# exixe_pogo.net
KiCad netlist of a schematic drawn in EAGLE
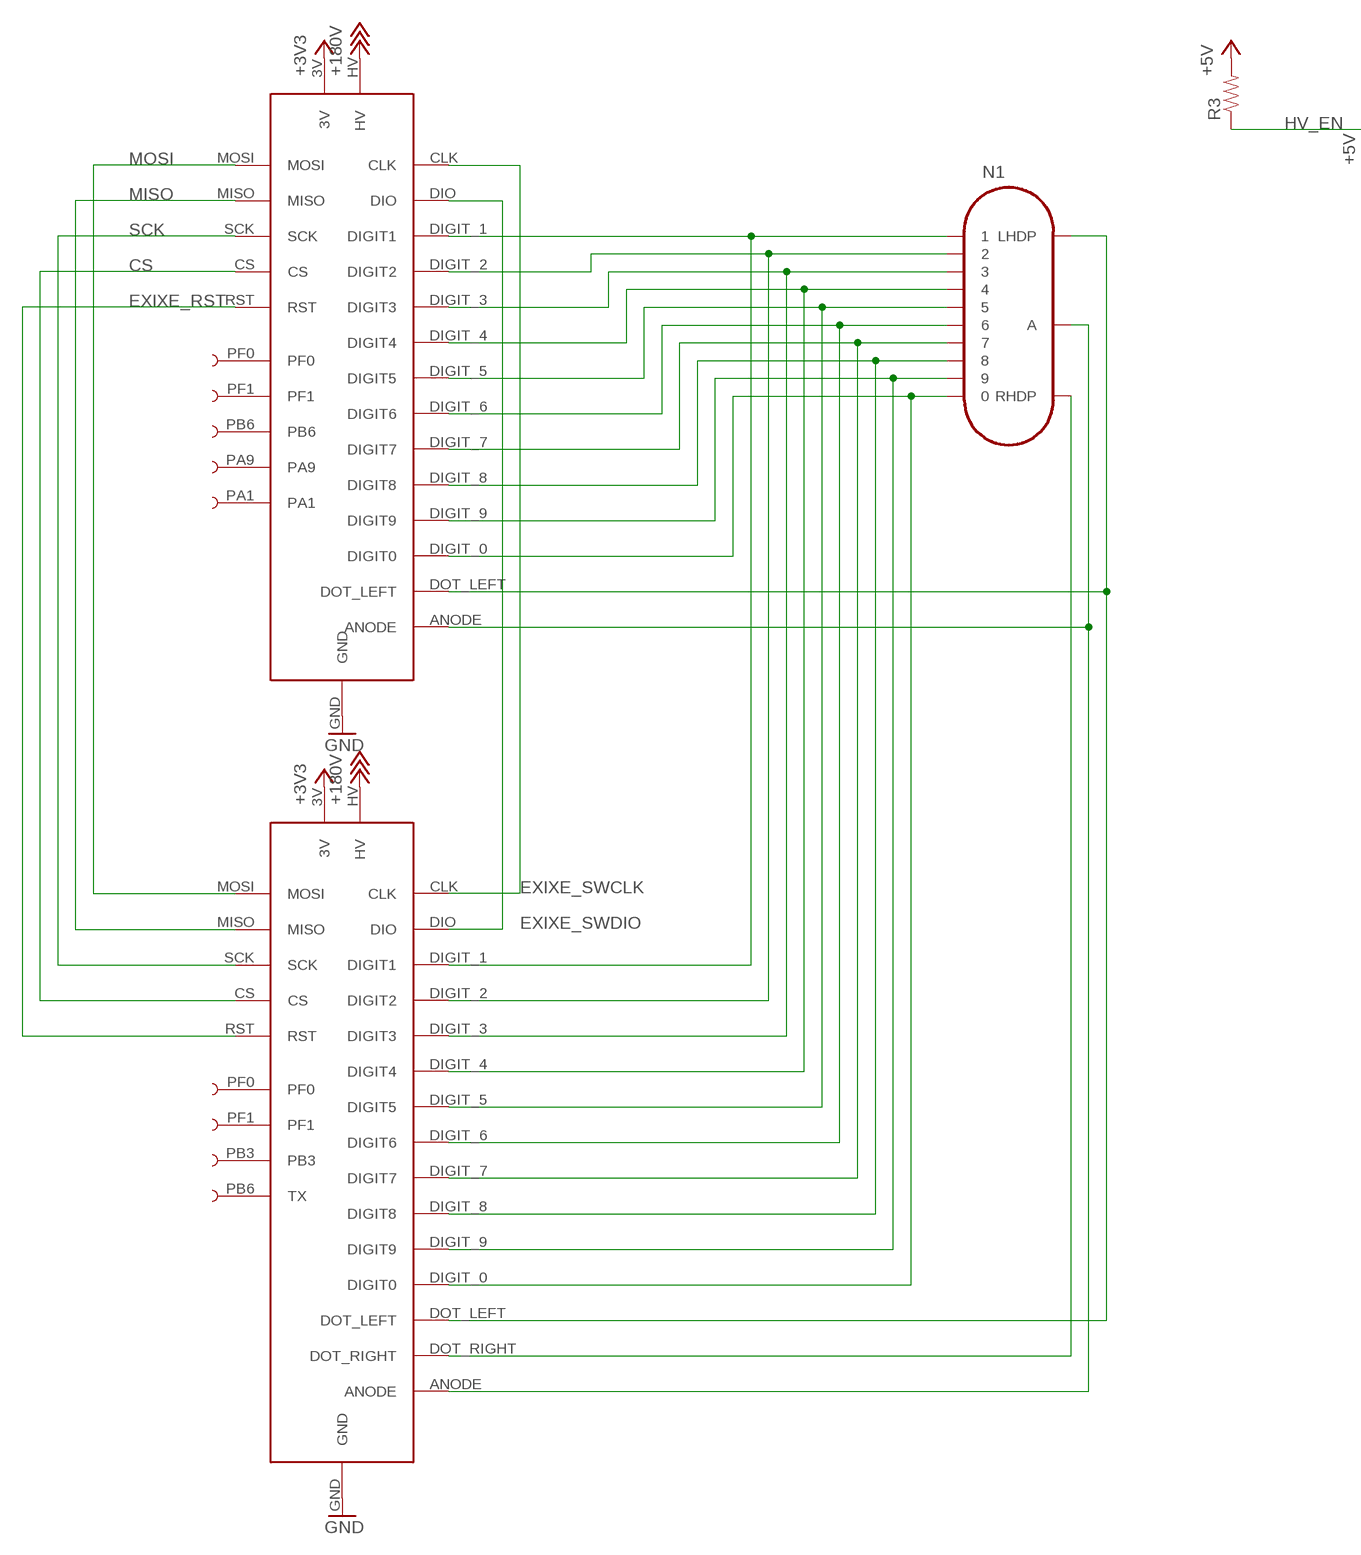
[diagram p0: schematic, sheet 1, part 1 of 2]
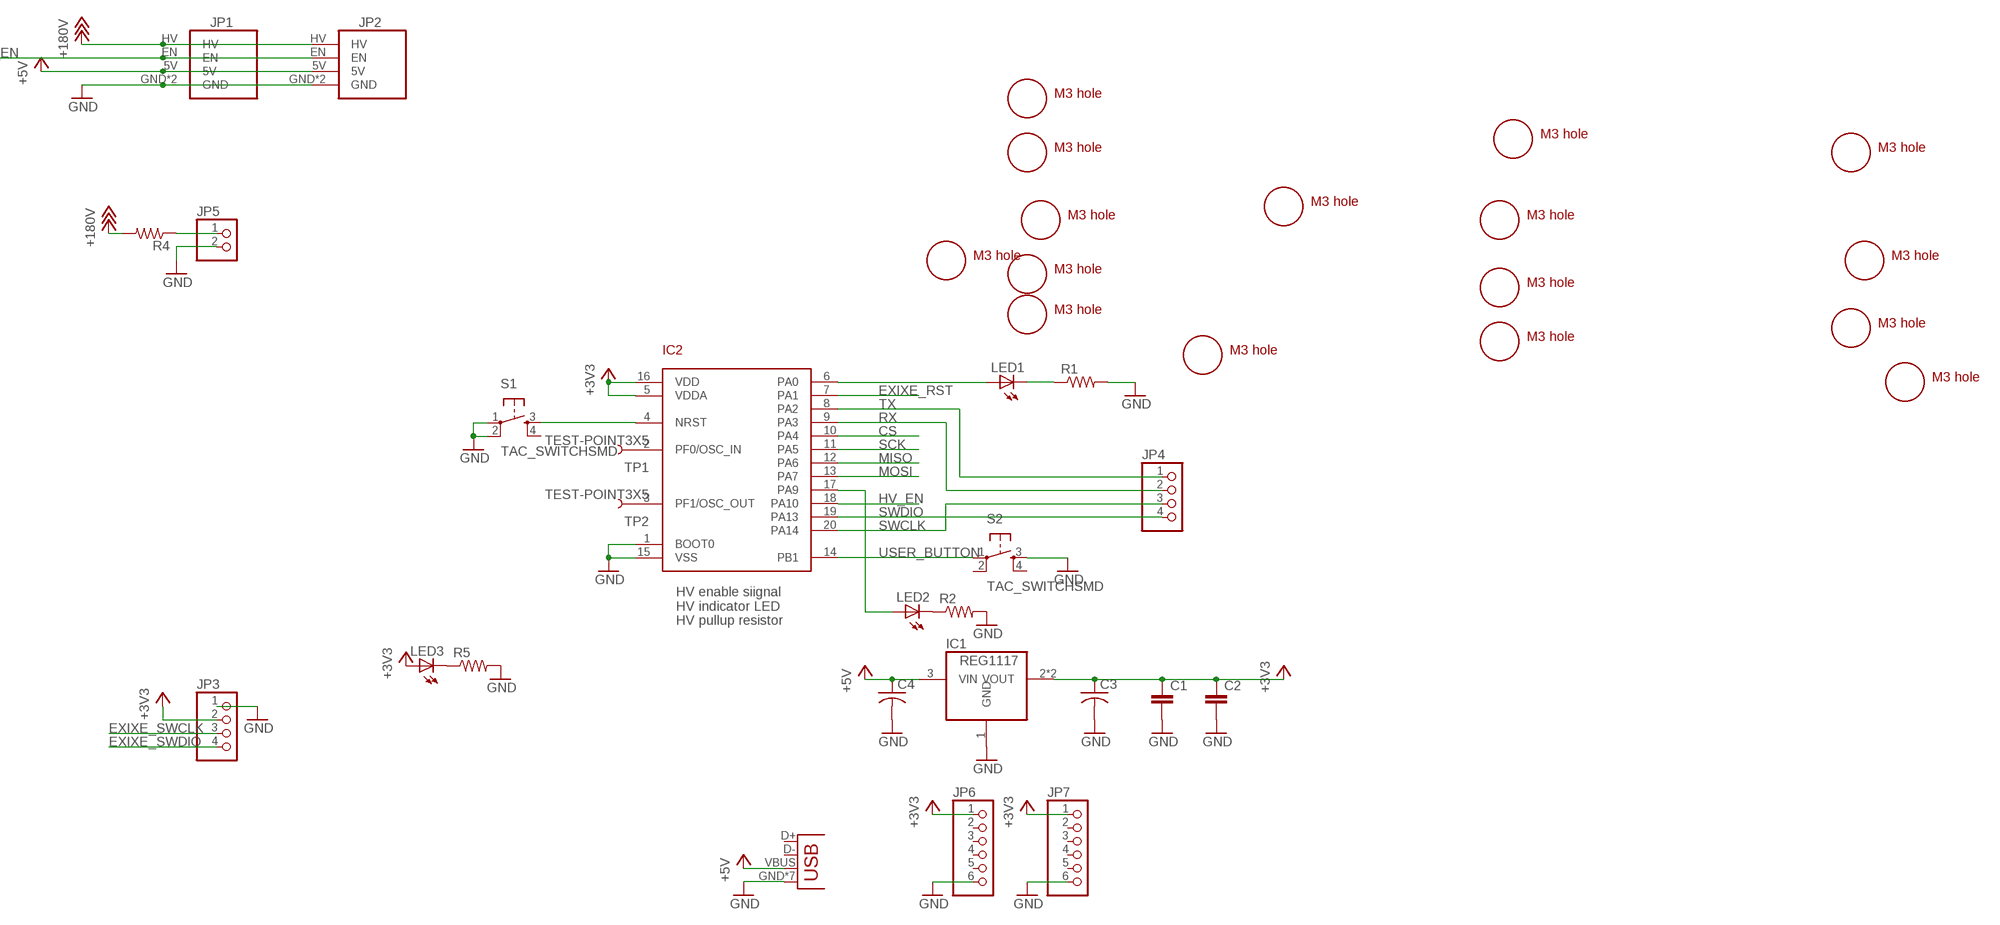
[diagram p1: schematic, sheet 1, part 2 of 2]

(export (version "E")
  (design (tool "Eeschema 10.0.6"))
  (components
    (comp (ref "C1")
      (value "CAP0805")
      (footprint "eagle-import:0805")
      (libsource (lib "eagle-import") (part "CAP0805"))
    )
    (comp (ref "C2")
      (value "CAP0805")
      (footprint "eagle-import:0805")
      (libsource (lib "eagle-import") (part "CAP0805"))
    )
    (comp (ref "C3")
      (value "C-USC1210")
      (footprint "eagle-import:C1210")
      (libsource (lib "eagle-import") (part "C-USC1210"))
    )
    (comp (ref "C4")
      (value "C-USC1210")
      (footprint "eagle-import:C1210")
      (libsource (lib "eagle-import") (part "C-USC1210"))
    )
    (comp (ref "IC1")
      (value "REG1117")
      (footprint "eagle-import:SOT223")
      (libsource (lib "eagle-import") (part "REG1117"))
    )
    (comp (ref "IC2")
      (value "STM32F030F4")
      (footprint "eagle-import:TSSOP20")
      (libsource (lib "eagle-import") (part "STM32F030F4"))
    )
    (comp (ref "JP1")
      (value "EBAY_MODULEEBAY")
      (footprint "eagle-import:EBAY_PKG")
      (libsource (lib "eagle-import") (part "EBAY_MODULEEBAY"))
    )
    (comp (ref "JP2")
      (value "EBAY_MODULETAOBAO")
      (footprint "eagle-import:TAOBAO_PKG")
      (libsource (lib "eagle-import") (part "EBAY_MODULETAOBAO"))
    )
    (comp (ref "JP3")
      (value "PINHD-1X4")
      (footprint "eagle-import:1X04")
      (libsource (lib "eagle-import") (part "PINHD-1X4"))
    )
    (comp (ref "JP4")
      (value "PINHD-1X4")
      (footprint "eagle-import:1X04")
      (libsource (lib "eagle-import") (part "PINHD-1X4"))
    )
    (comp (ref "JP5")
      (value "PINHD-1X2")
      (footprint "eagle-import:1X02")
      (libsource (lib "eagle-import") (part "PINHD-1X2"))
    )
    (comp (ref "JP6")
      (value "PINHD-1X6")
      (footprint "eagle-import:1X06")
      (libsource (lib "eagle-import") (part "PINHD-1X6"))
    )
    (comp (ref "JP7")
      (value "PINHD-1X6")
      (footprint "eagle-import:1X06")
      (libsource (lib "eagle-import") (part "PINHD-1X6"))
    )
    (comp (ref "LED1")
      (value "LEDCHIP-LED0805")
      (footprint "eagle-import:CHIP-LED0805")
      (libsource (lib "eagle-import") (part "LEDCHIP-LED0805"))
    )
    (comp (ref "LED2")
      (value "LEDCHIP-LED0805")
      (footprint "eagle-import:CHIP-LED0805")
      (libsource (lib "eagle-import") (part "LEDCHIP-LED0805"))
    )
    (comp (ref "LED3")
      (value "LEDCHIP-LED0805")
      (footprint "eagle-import:CHIP-LED0805")
      (libsource (lib "eagle-import") (part "LEDCHIP-LED0805"))
    )
    (comp (ref "N1")
      (value "IN-14")
      (footprint "eagle-import:IN-14")
      (libsource (lib "eagle-import") (part "IN-14"))
    )
    (comp (ref "R1")
      (value "RESISTOR0805-RES")
      (footprint "eagle-import:0805")
      (libsource (lib "eagle-import") (part "RESISTOR0805-RES"))
    )
    (comp (ref "R2")
      (value "RESISTOR0805-RES")
      (footprint "eagle-import:0805")
      (libsource (lib "eagle-import") (part "RESISTOR0805-RES"))
    )
    (comp (ref "R3")
      (value "RESISTOR0805-RES")
      (footprint "eagle-import:0805")
      (libsource (lib "eagle-import") (part "RESISTOR0805-RES"))
    )
    (comp (ref "R4")
      (value "RESISTOR0805-RES")
      (footprint "eagle-import:0805")
      (libsource (lib "eagle-import") (part "RESISTOR0805-RES"))
    )
    (comp (ref "R5")
      (value "RESISTOR0805-RES")
      (footprint "eagle-import:0805")
      (libsource (lib "eagle-import") (part "RESISTOR0805-RES"))
    )
    (comp (ref "S1")
      (value "TAC_SWITCHSMD")
      (footprint "eagle-import:TACTILE-SWITCH-SMD")
      (libsource (lib "eagle-import") (part "TAC_SWITCHSMD"))
    )
    (comp (ref "S2")
      (value "TAC_SWITCHSMD")
      (footprint "eagle-import:TACTILE-SWITCH-SMD")
      (libsource (lib "eagle-import") (part "TAC_SWITCHSMD"))
    )
    (comp (ref "TP1")
      (value "TEST-POINT3X5")
      (footprint "eagle-import:PAD.03X.05")
      (libsource (lib "eagle-import") (part "TEST-POINT3X5"))
    )
    (comp (ref "TP2")
      (value "TEST-POINT3X5")
      (footprint "eagle-import:PAD.03X.05")
      (libsource (lib "eagle-import") (part "TEST-POINT3X5"))
    )
    (comp (ref "TP3")
      (value "TEST-POINT3X5")
      (footprint "eagle-import:PAD.03X.05")
      (libsource (lib "eagle-import") (part "TEST-POINT3X5"))
    )
    (comp (ref "TP4")
      (value "TEST-POINT3X5")
      (footprint "eagle-import:PAD.03X.05")
      (libsource (lib "eagle-import") (part "TEST-POINT3X5"))
    )
    (comp (ref "TP5")
      (value "TEST-POINT3X5")
      (footprint "eagle-import:PAD.03X.05")
      (libsource (lib "eagle-import") (part "TEST-POINT3X5"))
    )
    (comp (ref "TP6")
      (value "TEST-POINT3X5")
      (footprint "eagle-import:PAD.03X.05")
      (libsource (lib "eagle-import") (part "TEST-POINT3X5"))
    )
    (comp (ref "TP7")
      (value "TEST-POINT3X5")
      (footprint "eagle-import:PAD.03X.05")
      (libsource (lib "eagle-import") (part "TEST-POINT3X5"))
    )
    (comp (ref "TP8")
      (value "TEST-POINT3X5")
      (footprint "eagle-import:PAD.03X.05")
      (libsource (lib "eagle-import") (part "TEST-POINT3X5"))
    )
    (comp (ref "TP9")
      (value "TEST-POINT3X5")
      (footprint "eagle-import:PAD.03X.05")
      (libsource (lib "eagle-import") (part "TEST-POINT3X5"))
    )
    (comp (ref "TP10")
      (value "TEST-POINT3X5")
      (footprint "eagle-import:PAD.03X.05")
      (libsource (lib "eagle-import") (part "TEST-POINT3X5"))
    )
    (comp (ref "TP11")
      (value "TEST-POINT3X5")
      (footprint "eagle-import:PAD.03X.05")
      (libsource (lib "eagle-import") (part "TEST-POINT3X5"))
    )
    (comp (ref "U$1")
      (value "EXIXE12_POGO")
      (footprint "eagle-import:EXIXE12_PAC")
      (libsource (lib "eagle-import") (part "EXIXE12_POGO"))
    )
    (comp (ref "U$2")
      (value "EXIXE14_POGO")
      (footprint "eagle-import:EXIXE14_PAC")
      (libsource (lib "eagle-import") (part "EXIXE14_POGO"))
    )
    (comp (ref "U$3")
      (value "M3_MOUNTING_HOLE")
      (footprint "eagle-import:M3_MOUNTING_HOLE_PACK")
      (libsource (lib "eagle-import") (part "M3_MOUNTING_HOLE"))
    )
    (comp (ref "U$4")
      (value "M3_MOUNTING_HOLE")
      (footprint "eagle-import:M3_MOUNTING_HOLE_PACK")
      (libsource (lib "eagle-import") (part "M3_MOUNTING_HOLE"))
    )
    (comp (ref "U$5")
      (value "M3_MOUNTING_HOLE")
      (footprint "eagle-import:M3_MOUNTING_HOLE_PACK")
      (libsource (lib "eagle-import") (part "M3_MOUNTING_HOLE"))
    )
    (comp (ref "U$6")
      (value "M3_MOUNTING_HOLE")
      (footprint "eagle-import:M3_MOUNTING_HOLE_PACK")
      (libsource (lib "eagle-import") (part "M3_MOUNTING_HOLE"))
    )
    (comp (ref "U$7")
      (value "M3_MOUNTING_HOLE")
      (footprint "eagle-import:M3_MOUNTING_HOLE_PACK")
      (libsource (lib "eagle-import") (part "M3_MOUNTING_HOLE"))
    )
    (comp (ref "U$8")
      (value "M3_MOUNTING_HOLE")
      (footprint "eagle-import:M3_MOUNTING_HOLE_PACK")
      (libsource (lib "eagle-import") (part "M3_MOUNTING_HOLE"))
    )
    (comp (ref "U$9")
      (value "M3_MOUNTING_HOLE")
      (footprint "eagle-import:M3_MOUNTING_HOLE_PACK")
      (libsource (lib "eagle-import") (part "M3_MOUNTING_HOLE"))
    )
    (comp (ref "U$10")
      (value "M3_MOUNTING_HOLE")
      (footprint "eagle-import:M3_MOUNTING_HOLE_PACK")
      (libsource (lib "eagle-import") (part "M3_MOUNTING_HOLE"))
    )
    (comp (ref "U$11")
      (value "M3_MOUNTING_HOLE")
      (footprint "eagle-import:M3_MOUNTING_HOLE_PACK")
      (libsource (lib "eagle-import") (part "M3_MOUNTING_HOLE"))
    )
    (comp (ref "U$12")
      (value "M3_MOUNTING_HOLE")
      (footprint "eagle-import:M3_MOUNTING_HOLE_PACK")
      (libsource (lib "eagle-import") (part "M3_MOUNTING_HOLE"))
    )
    (comp (ref "U$13")
      (value "M3_MOUNTING_HOLE")
      (footprint "eagle-import:M3_MOUNTING_HOLE_PACK")
      (libsource (lib "eagle-import") (part "M3_MOUNTING_HOLE"))
    )
    (comp (ref "U$14")
      (value "M3_MOUNTING_HOLE")
      (footprint "eagle-import:M3_MOUNTING_HOLE_PACK")
      (libsource (lib "eagle-import") (part "M3_MOUNTING_HOLE"))
    )
    (comp (ref "U$15")
      (value "M3_MOUNTING_HOLE")
      (footprint "eagle-import:M3_MOUNTING_HOLE_PACK")
      (libsource (lib "eagle-import") (part "M3_MOUNTING_HOLE"))
    )
    (comp (ref "U$16")
      (value "M3_MOUNTING_HOLE")
      (footprint "eagle-import:M3_MOUNTING_HOLE_PACK")
      (libsource (lib "eagle-import") (part "M3_MOUNTING_HOLE"))
    )
    (comp (ref "U$17")
      (value "M3_MOUNTING_HOLE")
      (footprint "eagle-import:M3_MOUNTING_HOLE_PACK")
      (libsource (lib "eagle-import") (part "M3_MOUNTING_HOLE"))
    )
    (comp (ref "U$18")
      (value "M3_MOUNTING_HOLE")
      (footprint "eagle-import:M3_MOUNTING_HOLE_PACK")
      (libsource (lib "eagle-import") (part "M3_MOUNTING_HOLE"))
    )
    (comp (ref "X1")
      (value "USB-MICROB")
      (footprint "eagle-import:USB-MICROB")
      (libsource (lib "eagle-import") (part "USB-MICROB"))
    )
  )
  (nets
    (net (code "1") (name "+3V3") (class "Default")
      (node (ref "C1") (pin "1") (pinfunction "1_1") (pintype "passive"))
      (node (ref "C2") (pin "1") (pinfunction "1_1") (pintype "passive"))
      (node (ref "C3") (pin "1") (pinfunction "1_1") (pintype "passive"))
      (node (ref "IC1") (pin "2") (pinfunction "VOUT_2") (pintype "output"))
      (node (ref "IC1") (pin "4") (pinfunction "VOUT_4") (pintype "output"))
      (node (ref "IC2") (pin "16") (pinfunction "VDD_16") (pintype "bidirectional"))
      (node (ref "IC2") (pin "5") (pinfunction "VDDA_5") (pintype "bidirectional"))
      (node (ref "JP3") (pin "2") (pinfunction "2_2") (pintype "passive"))
      (node (ref "JP6") (pin "1") (pinfunction "1_1") (pintype "passive"))
      (node (ref "JP7") (pin "1") (pinfunction "1_1") (pintype "passive"))
      (node (ref "LED3") (pin "A") (pinfunction "A_A") (pintype "passive"))
      (node (ref "U$1") (pin "3V") (pinfunction "3V_3V") (pintype "bidirectional"))
      (node (ref "U$2") (pin "3V") (pinfunction "3V_3V") (pintype "bidirectional"))
    )
    (net (code "2") (name "+5V") (class "Default")
      (node (ref "C4") (pin "1") (pinfunction "1_1") (pintype "passive"))
      (node (ref "IC1") (pin "3") (pinfunction "VIN_3") (pintype "input"))
      (node (ref "JP1") (pin "5V") (pinfunction "5V_5V") (pintype "bidirectional"))
      (node (ref "JP2") (pin "5V") (pinfunction "5V_5V") (pintype "bidirectional"))
      (node (ref "R3") (pin "2") (pinfunction "2_2") (pintype "passive"))
      (node (ref "X1") (pin "VBUS") (pinfunction "VBUS_VBUS") (pintype "bidirectional"))
    )
    (net (code "3") (name "+180V") (class "Default")
      (node (ref "JP1") (pin "HV") (pinfunction "HV_HV") (pintype "bidirectional"))
      (node (ref "JP2") (pin "HV") (pinfunction "HV_HV") (pintype "bidirectional"))
      (node (ref "R4") (pin "2") (pinfunction "2_2") (pintype "passive"))
      (node (ref "U$1") (pin "HV") (pinfunction "HV_HV") (pintype "bidirectional"))
      (node (ref "U$2") (pin "HV") (pinfunction "HV_HV") (pintype "bidirectional"))
    )
    (net (code "4") (name "/CS") (class "Default")
      (node (ref "IC2") (pin "10") (pinfunction "PA4_10") (pintype "bidirectional"))
      (node (ref "U$1") (pin "CS") (pinfunction "CS_CS") (pintype "bidirectional"))
      (node (ref "U$2") (pin "CS") (pinfunction "CS_CS") (pintype "bidirectional"))
    )
    (net (code "5") (name "/EXIXE_RST") (class "Default")
      (node (ref "IC2") (pin "7") (pinfunction "PA1_7") (pintype "bidirectional"))
      (node (ref "U$1") (pin "RST") (pinfunction "RST_RST") (pintype "bidirectional"))
      (node (ref "U$2") (pin "RST") (pinfunction "RST_RST") (pintype "bidirectional"))
    )
    (net (code "6") (name "/EXIXE_SWCLK") (class "Default")
      (node (ref "JP3") (pin "3") (pinfunction "3_3") (pintype "passive"))
      (node (ref "U$1") (pin "CLK") (pinfunction "CLK_CLK") (pintype "bidirectional"))
      (node (ref "U$2") (pin "CLK") (pinfunction "CLK_CLK") (pintype "bidirectional"))
    )
    (net (code "7") (name "/EXIXE_SWDIO") (class "Default")
      (node (ref "JP3") (pin "4") (pinfunction "4_4") (pintype "passive"))
      (node (ref "U$1") (pin "DIO") (pinfunction "DIO_DIO") (pintype "bidirectional"))
      (node (ref "U$2") (pin "DIO") (pinfunction "DIO_DIO") (pintype "bidirectional"))
    )
    (net (code "8") (name "/HV_EN") (class "Default")
      (node (ref "IC2") (pin "18") (pinfunction "PA10_18") (pintype "bidirectional"))
      (node (ref "JP1") (pin "EN") (pinfunction "EN_EN") (pintype "bidirectional"))
      (node (ref "JP2") (pin "EN") (pinfunction "EN_EN") (pintype "bidirectional"))
      (node (ref "R3") (pin "1") (pinfunction "1_1") (pintype "passive"))
    )
    (net (code "9") (name "/MISO") (class "Default")
      (node (ref "IC2") (pin "12") (pinfunction "PA6_12") (pintype "bidirectional"))
      (node (ref "U$1") (pin "MISO") (pinfunction "MISO_MISO") (pintype "bidirectional"))
      (node (ref "U$2") (pin "MISO") (pinfunction "MISO_MISO") (pintype "bidirectional"))
    )
    (net (code "10") (name "/MOSI") (class "Default")
      (node (ref "IC2") (pin "13") (pinfunction "PA7_13") (pintype "bidirectional"))
      (node (ref "U$1") (pin "MOSI") (pinfunction "MOSI_MOSI") (pintype "bidirectional"))
      (node (ref "U$2") (pin "MOSI") (pinfunction "MOSI_MOSI") (pintype "bidirectional"))
    )
    (net (code "11") (name "/RX") (class "Default")
      (node (ref "IC2") (pin "9") (pinfunction "PA3_9") (pintype "bidirectional"))
      (node (ref "JP4") (pin "2") (pinfunction "2_2") (pintype "passive"))
    )
    (net (code "12") (name "/SCK") (class "Default")
      (node (ref "IC2") (pin "11") (pinfunction "PA5_11") (pintype "bidirectional"))
      (node (ref "U$1") (pin "SCK") (pinfunction "SCK_SCK") (pintype "bidirectional"))
      (node (ref "U$2") (pin "SCK") (pinfunction "SCK_SCK") (pintype "bidirectional"))
    )
    (net (code "13") (name "/SWCLK") (class "Default")
      (node (ref "IC2") (pin "20") (pinfunction "PA14_20") (pintype "bidirectional"))
      (node (ref "JP4") (pin "3") (pinfunction "3_3") (pintype "passive"))
    )
    (net (code "14") (name "/SWDIO") (class "Default")
      (node (ref "IC2") (pin "19") (pinfunction "PA13_19") (pintype "bidirectional"))
      (node (ref "JP4") (pin "4") (pinfunction "4_4") (pintype "passive"))
    )
    (net (code "15") (name "/TX") (class "Default")
      (node (ref "IC2") (pin "8") (pinfunction "PA2_8") (pintype "bidirectional"))
      (node (ref "JP4") (pin "1") (pinfunction "1_1") (pintype "passive"))
    )
    (net (code "16") (name "/USER_BUTTON") (class "Default")
      (node (ref "IC2") (pin "14") (pinfunction "PB1_14") (pintype "bidirectional"))
      (node (ref "S2") (pin "1") (pinfunction "1_1") (pintype "passive"))
    )
    (net (code "17") (name "GND") (class "Default")
      (node (ref "C1") (pin "2") (pinfunction "2_2") (pintype "passive"))
      (node (ref "C2") (pin "2") (pinfunction "2_2") (pintype "passive"))
      (node (ref "C3") (pin "2") (pinfunction "2_2") (pintype "passive"))
      (node (ref "C4") (pin "2") (pinfunction "2_2") (pintype "passive"))
      (node (ref "IC1") (pin "1") (pinfunction "GND_1") (pintype "power_in"))
      (node (ref "IC2") (pin "1") (pinfunction "BOOT0_1") (pintype "bidirectional"))
      (node (ref "IC2") (pin "15") (pinfunction "VSS_15") (pintype "bidirectional"))
      (node (ref "JP1") (pin "GND") (pinfunction "GND_GND") (pintype "bidirectional"))
      (node (ref "JP1") (pin "GND2") (pinfunction "GND_GND2") (pintype "bidirectional"))
      (node (ref "JP2") (pin "GND") (pinfunction "GND_GND") (pintype "bidirectional"))
      (node (ref "JP2") (pin "GND2") (pinfunction "GND_GND2") (pintype "bidirectional"))
      (node (ref "JP3") (pin "1") (pinfunction "1_1") (pintype "passive"))
      (node (ref "JP5") (pin "2") (pinfunction "2_2") (pintype "passive"))
      (node (ref "JP6") (pin "6") (pinfunction "6_6") (pintype "passive"))
      (node (ref "JP7") (pin "6") (pinfunction "6_6") (pintype "passive"))
      (node (ref "R1") (pin "2") (pinfunction "2_2") (pintype "passive"))
      (node (ref "R2") (pin "2") (pinfunction "2_2") (pintype "passive"))
      (node (ref "R5") (pin "2") (pinfunction "2_2") (pintype "passive"))
      (node (ref "S1") (pin "1") (pinfunction "1_1") (pintype "passive"))
      (node (ref "S1") (pin "2") (pinfunction "2_2") (pintype "passive"))
      (node (ref "S2") (pin "3") (pinfunction "3_3") (pintype "passive"))
      (node (ref "U$1") (pin "GND") (pinfunction "GND_GND") (pintype "bidirectional"))
      (node (ref "U$2") (pin "GND") (pinfunction "GND_GND") (pintype "bidirectional"))
      (node (ref "X1") (pin "GND") (pinfunction "GND_GND") (pintype "bidirectional"))
      (node (ref "X1") (pin "P1") (pinfunction "GND_P1") (pintype "bidirectional"))
      (node (ref "X1") (pin "P2") (pinfunction "GND_P2") (pintype "bidirectional"))
      (node (ref "X1") (pin "P3") (pinfunction "GND_P3") (pintype "bidirectional"))
      (node (ref "X1") (pin "P4") (pinfunction "GND_P4") (pintype "bidirectional"))
      (node (ref "X1") (pin "P5") (pinfunction "GND_P5") (pintype "bidirectional"))
      (node (ref "X1") (pin "P6") (pinfunction "GND_P6") (pintype "bidirectional"))
    )
    (net (code "18") (name "Net-(IC2-NRST)") (class "Default")
      (node (ref "IC2") (pin "4") (pinfunction "NRST_4") (pintype "bidirectional"))
      (node (ref "S1") (pin "3") (pinfunction "3_3") (pintype "passive"))
    )
    (net (code "19") (name "Net-(IC2-PA0)") (class "Default")
      (node (ref "IC2") (pin "6") (pinfunction "PA0_6") (pintype "bidirectional"))
      (node (ref "LED1") (pin "A") (pinfunction "A_A") (pintype "passive"))
    )
    (net (code "20") (name "Net-(IC2-PA9)") (class "Default")
      (node (ref "IC2") (pin "17") (pinfunction "PA9_17") (pintype "bidirectional"))
      (node (ref "LED2") (pin "A") (pinfunction "A_A") (pintype "passive"))
    )
    (net (code "21") (name "Net-(IC2-PF0{slash}OSC_IN)") (class "Default")
      (node (ref "IC2") (pin "2") (pinfunction "PF0/OSC_IN_2") (pintype "bidirectional"))
      (node (ref "TP1") (pin "P$1") (pinfunction "1_P$1") (pintype "bidirectional"))
    )
    (net (code "22") (name "Net-(IC2-PF1{slash}OSC_OUT)") (class "Default")
      (node (ref "IC2") (pin "3") (pinfunction "PF1/OSC_OUT_3") (pintype "bidirectional"))
      (node (ref "TP2") (pin "P$1") (pinfunction "1_P$1") (pintype "bidirectional"))
    )
    (net (code "23") (name "Net-(JP5-Pad1)") (class "Default")
      (node (ref "JP5") (pin "1") (pinfunction "1_1") (pintype "passive"))
      (node (ref "R4") (pin "1") (pinfunction "1_1") (pintype "passive"))
    )
    (net (code "24") (name "Net-(LED1-PadC)") (class "Default")
      (node (ref "LED1") (pin "C") (pinfunction "C_C") (pintype "passive"))
      (node (ref "R1") (pin "1") (pinfunction "1_1") (pintype "passive"))
    )
    (net (code "25") (name "Net-(LED2-PadC)") (class "Default")
      (node (ref "LED2") (pin "C") (pinfunction "C_C") (pintype "passive"))
      (node (ref "R2") (pin "1") (pinfunction "1_1") (pintype "passive"))
    )
    (net (code "26") (name "Net-(LED3-PadC)") (class "Default")
      (node (ref "LED3") (pin "C") (pinfunction "C_C") (pintype "passive"))
      (node (ref "R5") (pin "1") (pinfunction "1_1") (pintype "passive"))
    )
    (net (code "27") (name "Net-(N1-PadA)") (class "Default")
      (node (ref "N1") (pin "A") (pinfunction "A_A") (pintype "bidirectional"))
      (node (ref "U$1") (pin "ANODE") (pinfunction "ANODE_ANODE") (pintype "bidirectional"))
      (node (ref "U$2") (pin "ANODE") (pinfunction "ANODE_ANODE") (pintype "bidirectional"))
    )
    (net (code "28") (name "Net-(N1-PadLHDP)") (class "Default")
      (node (ref "N1") (pin "LHDP") (pinfunction "LHDP_LHDP") (pintype "bidirectional"))
      (node (ref "U$1") (pin "DOT_LEFT") (pinfunction "DOT_LEFT_DOT_LEFT") (pintype "bidirectional"))
      (node (ref "U$2") (pin "DOT_LEFT") (pinfunction "DOT_LEFT_DOT_LEFT") (pintype "bidirectional"))
    )
    (net (code "29") (name "Net-(N1-PadRHDP)") (class "Default")
      (node (ref "N1") (pin "RHDP") (pinfunction "RHDP_RHDP") (pintype "bidirectional"))
      (node (ref "U$2") (pin "DOT_RIGHT") (pinfunction "DOT_RIGHT_DOT_RIGHT") (pintype "bidirectional"))
    )
    (net (code "30") (name "Net-(TP3-1)") (class "Default")
      (node (ref "TP3") (pin "P$1") (pinfunction "1_P$1") (pintype "bidirectional"))
      (node (ref "U$1") (pin "PF0") (pinfunction "PF0_PF0") (pintype "bidirectional"))
    )
    (net (code "31") (name "Net-(TP4-1)") (class "Default")
      (node (ref "TP4") (pin "P$1") (pinfunction "1_P$1") (pintype "bidirectional"))
      (node (ref "U$1") (pin "PF1") (pinfunction "PF1_PF1") (pintype "bidirectional"))
    )
    (net (code "32") (name "Net-(TP5-1)") (class "Default")
      (node (ref "TP5") (pin "P$1") (pinfunction "1_P$1") (pintype "bidirectional"))
      (node (ref "U$1") (pin "PB6") (pinfunction "PB6_PB6") (pintype "bidirectional"))
    )
    (net (code "33") (name "Net-(TP6-1)") (class "Default")
      (node (ref "TP6") (pin "P$1") (pinfunction "1_P$1") (pintype "bidirectional"))
      (node (ref "U$1") (pin "PA9") (pinfunction "PA9_PA9") (pintype "bidirectional"))
    )
    (net (code "34") (name "Net-(TP7-1)") (class "Default")
      (node (ref "TP7") (pin "P$1") (pinfunction "1_P$1") (pintype "bidirectional"))
      (node (ref "U$1") (pin "PA1") (pinfunction "PA1_PA1") (pintype "bidirectional"))
    )
    (net (code "35") (name "Net-(TP8-1)") (class "Default")
      (node (ref "TP8") (pin "P$1") (pinfunction "1_P$1") (pintype "bidirectional"))
      (node (ref "U$2") (pin "PF0") (pinfunction "PF0_PF0") (pintype "bidirectional"))
    )
    (net (code "36") (name "Net-(TP9-1)") (class "Default")
      (node (ref "TP9") (pin "P$1") (pinfunction "1_P$1") (pintype "bidirectional"))
      (node (ref "U$2") (pin "PF1") (pinfunction "PF1_PF1") (pintype "bidirectional"))
    )
    (net (code "37") (name "Net-(TP10-1)") (class "Default")
      (node (ref "TP10") (pin "P$1") (pinfunction "1_P$1") (pintype "bidirectional"))
      (node (ref "U$2") (pin "PB3") (pinfunction "PB3_PB3") (pintype "bidirectional"))
    )
    (net (code "38") (name "Net-(TP11-1)") (class "Default")
      (node (ref "TP11") (pin "P$1") (pinfunction "1_P$1") (pintype "bidirectional"))
      (node (ref "U$2") (pin "PB6") (pinfunction "TX_PB6") (pintype "bidirectional"))
    )
    (net (code "39") (name "Net-(U$1-DIGIT0)") (class "Default")
      (node (ref "N1") (pin "0") (pinfunction "0_0") (pintype "bidirectional"))
      (node (ref "U$1") (pin "DIGIT_0") (pinfunction "DIGIT0_DIGIT_0") (pintype "bidirectional"))
      (node (ref "U$2") (pin "DIGIT_0") (pinfunction "DIGIT0_DIGIT_0") (pintype "bidirectional"))
    )
    (net (code "40") (name "Net-(U$1-DIGIT1)") (class "Default")
      (node (ref "N1") (pin "1") (pinfunction "1_1") (pintype "bidirectional"))
      (node (ref "U$1") (pin "DIGIT_1") (pinfunction "DIGIT1_DIGIT_1") (pintype "bidirectional"))
      (node (ref "U$2") (pin "DIGIT_1") (pinfunction "DIGIT1_DIGIT_1") (pintype "bidirectional"))
    )
    (net (code "41") (name "Net-(U$1-DIGIT2)") (class "Default")
      (node (ref "N1") (pin "2") (pinfunction "2_2") (pintype "bidirectional"))
      (node (ref "U$1") (pin "DIGIT_2") (pinfunction "DIGIT2_DIGIT_2") (pintype "bidirectional"))
      (node (ref "U$2") (pin "DIGIT_2") (pinfunction "DIGIT2_DIGIT_2") (pintype "bidirectional"))
    )
    (net (code "42") (name "Net-(U$1-DIGIT3)") (class "Default")
      (node (ref "N1") (pin "3") (pinfunction "3_3") (pintype "bidirectional"))
      (node (ref "U$1") (pin "DIGIT_3") (pinfunction "DIGIT3_DIGIT_3") (pintype "bidirectional"))
      (node (ref "U$2") (pin "DIGIT_3") (pinfunction "DIGIT3_DIGIT_3") (pintype "bidirectional"))
    )
    (net (code "43") (name "Net-(U$1-DIGIT4)") (class "Default")
      (node (ref "N1") (pin "4") (pinfunction "4_4") (pintype "bidirectional"))
      (node (ref "U$1") (pin "DIGIT_4") (pinfunction "DIGIT4_DIGIT_4") (pintype "bidirectional"))
      (node (ref "U$2") (pin "DIGIT_4") (pinfunction "DIGIT4_DIGIT_4") (pintype "bidirectional"))
    )
    (net (code "44") (name "Net-(U$1-DIGIT5)") (class "Default")
      (node (ref "N1") (pin "5") (pinfunction "5_5") (pintype "bidirectional"))
      (node (ref "U$1") (pin "DIGIT_5") (pinfunction "DIGIT5_DIGIT_5") (pintype "bidirectional"))
      (node (ref "U$2") (pin "DIGIT_5") (pinfunction "DIGIT5_DIGIT_5") (pintype "bidirectional"))
    )
    (net (code "45") (name "Net-(U$1-DIGIT6)") (class "Default")
      (node (ref "N1") (pin "6") (pinfunction "6_6") (pintype "bidirectional"))
      (node (ref "U$1") (pin "DIGIT_6") (pinfunction "DIGIT6_DIGIT_6") (pintype "bidirectional"))
      (node (ref "U$2") (pin "DIGIT_6") (pinfunction "DIGIT6_DIGIT_6") (pintype "bidirectional"))
    )
    (net (code "46") (name "Net-(U$1-DIGIT7)") (class "Default")
      (node (ref "N1") (pin "7") (pinfunction "7_7") (pintype "bidirectional"))
      (node (ref "U$1") (pin "DIGIT_7") (pinfunction "DIGIT7_DIGIT_7") (pintype "bidirectional"))
      (node (ref "U$2") (pin "DIGIT_7") (pinfunction "DIGIT7_DIGIT_7") (pintype "bidirectional"))
    )
    (net (code "47") (name "Net-(U$1-DIGIT8)") (class "Default")
      (node (ref "N1") (pin "8") (pinfunction "8_8") (pintype "bidirectional"))
      (node (ref "U$1") (pin "DIGIT_8") (pinfunction "DIGIT8_DIGIT_8") (pintype "bidirectional"))
      (node (ref "U$2") (pin "DIGIT_8") (pinfunction "DIGIT8_DIGIT_8") (pintype "bidirectional"))
    )
    (net (code "48") (name "Net-(U$1-DIGIT9)") (class "Default")
      (node (ref "N1") (pin "9") (pinfunction "9_9") (pintype "bidirectional"))
      (node (ref "U$1") (pin "DIGIT_9") (pinfunction "DIGIT9_DIGIT_9") (pintype "bidirectional"))
      (node (ref "U$2") (pin "DIGIT_9") (pinfunction "DIGIT9_DIGIT_9") (pintype "bidirectional"))
    )
    (net (code "49") (name "unconnected-(JP6-Pad2)") (class "Default")
      (node (ref "JP6") (pin "2") (pinfunction "2_2") (pintype "passive"))
    )
    (net (code "50") (name "unconnected-(JP6-Pad3)") (class "Default")
      (node (ref "JP6") (pin "3") (pinfunction "3_3") (pintype "passive"))
    )
    (net (code "51") (name "unconnected-(JP6-Pad4)") (class "Default")
      (node (ref "JP6") (pin "4") (pinfunction "4_4") (pintype "passive"))
    )
    (net (code "52") (name "unconnected-(JP6-Pad5)") (class "Default")
      (node (ref "JP6") (pin "5") (pinfunction "5_5") (pintype "passive"))
    )
    (net (code "53") (name "unconnected-(JP7-Pad2)") (class "Default")
      (node (ref "JP7") (pin "2") (pinfunction "2_2") (pintype "passive"))
    )
    (net (code "54") (name "unconnected-(JP7-Pad3)") (class "Default")
      (node (ref "JP7") (pin "3") (pinfunction "3_3") (pintype "passive"))
    )
    (net (code "55") (name "unconnected-(JP7-Pad4)") (class "Default")
      (node (ref "JP7") (pin "4") (pinfunction "4_4") (pintype "passive"))
    )
    (net (code "56") (name "unconnected-(JP7-Pad5)") (class "Default")
      (node (ref "JP7") (pin "5") (pinfunction "5_5") (pintype "passive"))
    )
    (net (code "57") (name "unconnected-(S1-Pad4)") (class "Default")
      (node (ref "S1") (pin "4") (pinfunction "4_4") (pintype "passive"))
    )
    (net (code "58") (name "unconnected-(S2-Pad2)") (class "Default")
      (node (ref "S2") (pin "2") (pinfunction "2_2") (pintype "passive"))
    )
    (net (code "59") (name "unconnected-(S2-Pad4)") (class "Default")
      (node (ref "S2") (pin "4") (pinfunction "4_4") (pintype "passive"))
    )
    (net (code "60") (name "unconnected-(X1-PadD+)") (class "Default")
      (node (ref "X1") (pin "D+") (pinfunction "D+_D+") (pintype "bidirectional"))
    )
    (net (code "61") (name "unconnected-(X1-PadD-)") (class "Default")
      (node (ref "X1") (pin "D-") (pinfunction "D-_D-") (pintype "bidirectional"))
    )
  )
)
